# Power.net
KiCad netlist of a schematic drawn in Altium Designer
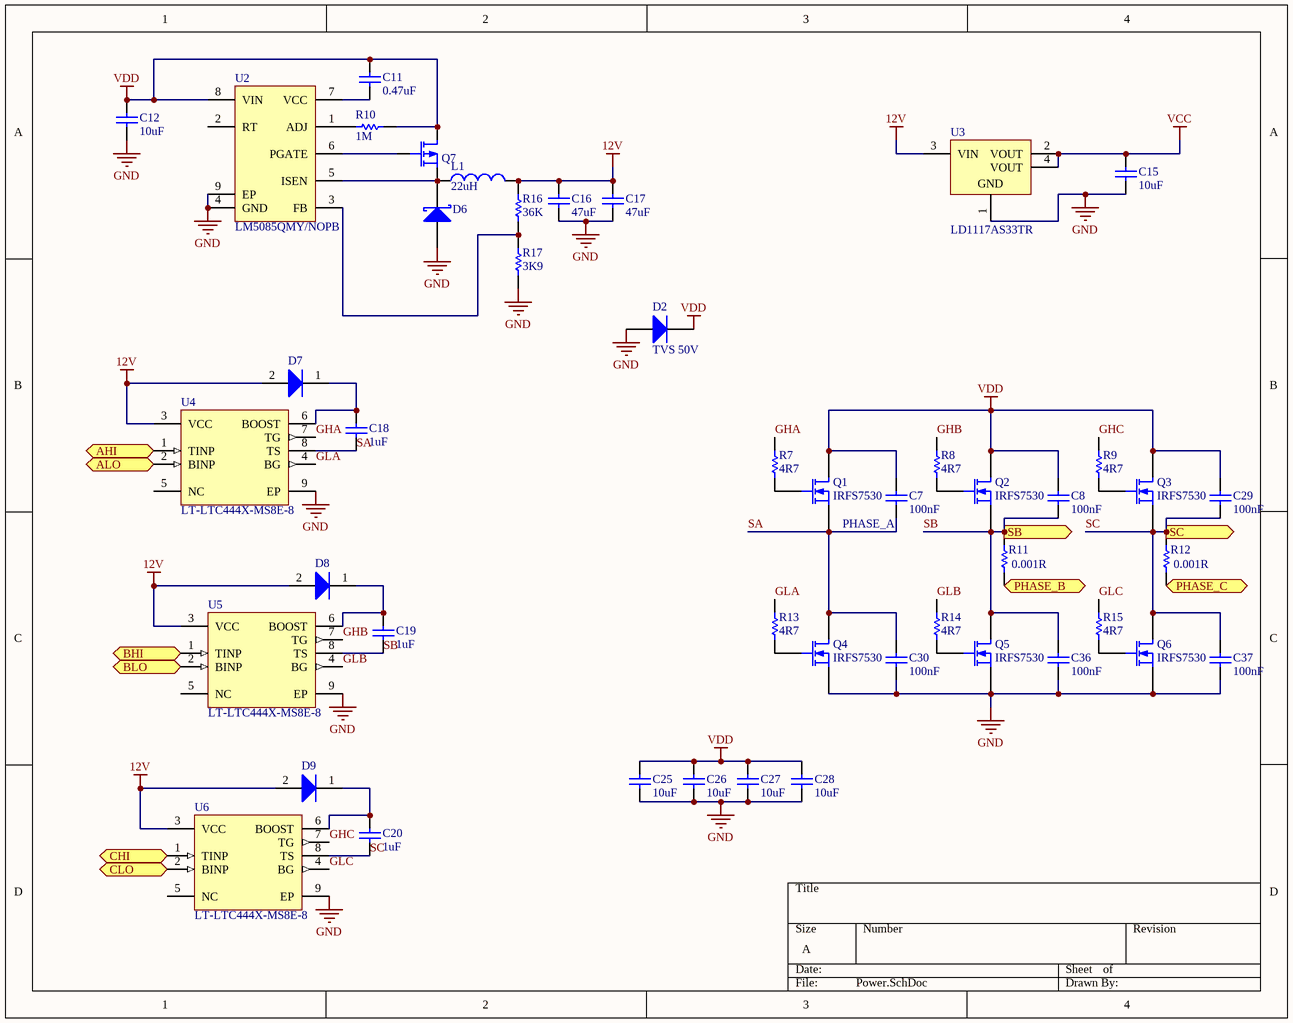
[diagram p0: Power.SchDoc]

(export (version "E")
  (design (tool "Eeschema 10.0.6"))
  (components
    (comp (ref "C7")
      (value "100nF")
      (footprint "CAPC0603(1608)100_L")
      (description "CAP 100nF 50V ±5% 0603 (1608 Metric) Thickness 1mm SMD")
      (fields (field (name "TOLERANCE") "Â±5%"))
      (libsource (lib "Altium Content Vault") (part "CAP"))
    )
    (comp (ref "C8")
      (value "100nF")
      (footprint "CAPC0603(1608)100_L")
      (description "CAP 100nF 50V ±5% 0603 (1608 Metric) Thickness 1mm SMD")
      (fields (field (name "TOLERANCE") "Â±5%"))
      (libsource (lib "Altium Content Vault") (part "CAP"))
    )
    (comp (ref "C11")
      (value "0.47uF")
      (footprint "CAPC0603(1608)100_L")
      (description "CAP 470nF 50V ±10% 0603 (1608 Metric) Thickness 1mm SMD")
      (fields (field (name "TOLERANCE") "Â±10%"))
      (libsource (lib "Altium Content Vault") (part "CAP"))
    )
    (comp (ref "C12")
      (value "10uF")
      (footprint "CAPC1206(3216)190_M")
      (description "CAP 10uF 50V Â±10% 1206 (3216 Metric) Thickness 1.9mm SMD")
      (fields (field (name "TOLERANCE") "Â±10%"))
      (libsource (lib "Altium Content Vault") (part "CMP-1037-04982-1"))
    )
    (comp (ref "C15")
      (value "10uF")
      (footprint "CAPC0603(1608)100_L")
      (description "CAP 10uF 6.3V ±10% 0603 (1608 Metric) Thickness 1mm SMD")
      (fields (field (name "TOLERANCE") "Â±10%"))
      (libsource (lib "Altium Content Vault") (part "CAP"))
    )
    (comp (ref "C16")
      (value "47uF")
      (footprint "CAPC1210(3225)280_L")
      (description "CAP 47uF 16V ±10% 1210 (3225 Metric) Thickness 2.8mm SMD")
      (fields (field (name "TOLERANCE") "Â±10%"))
      (libsource (lib "Altium Content Vault") (part "CAP"))
    )
    (comp (ref "C17")
      (value "47uF")
      (footprint "CAPC1210(3225)280_L")
      (description "CAP 47uF 16V ±10% 1210 (3225 Metric) Thickness 2.8mm SMD")
      (fields (field (name "TOLERANCE") "Â±10%"))
      (libsource (lib "Altium Content Vault") (part "CAP"))
    )
    (comp (ref "C18")
      (value "1uF")
      (footprint "CAPC0603(1608)100_M")
      (description "CAP 1uF 16V ±5% 0603 (1608 Metric) Thickness 1mm SMD")
      (fields (field (name "TOLERANCE") "Â±5%"))
      (libsource (lib "Altium Content Vault") (part "CAP"))
    )
    (comp (ref "C19")
      (value "1uF")
      (footprint "CAPC0603(1608)100_M")
      (description "CAP 1uF 16V ±5% 0603 (1608 Metric) Thickness 1mm SMD")
      (fields (field (name "TOLERANCE") "Â±5%"))
      (libsource (lib "Altium Content Vault") (part "CAP"))
    )
    (comp (ref "C20")
      (value "1uF")
      (footprint "CAPC0603(1608)100_M")
      (description "CAP 1uF 16V ±5% 0603 (1608 Metric) Thickness 1mm SMD")
      (fields (field (name "TOLERANCE") "Â±5%"))
      (libsource (lib "Altium Content Vault") (part "CAP"))
    )
    (comp (ref "C25")
      (value "10uF")
      (footprint "CAPC1206(3216)190_M")
      (description "CAP 10uF 50V Â±10% 1206 (3216 Metric) Thickness 1.9mm SMD")
      (fields (field (name "TOLERANCE") "Â±10%"))
      (libsource (lib "Altium Content Vault") (part "CMP-1037-04982-1"))
    )
    (comp (ref "C26")
      (value "10uF")
      (footprint "CAPC1206(3216)190_M")
      (description "CAP 10uF 50V Â±10% 1206 (3216 Metric) Thickness 1.9mm SMD")
      (fields (field (name "TOLERANCE") "Â±10%"))
      (libsource (lib "Altium Content Vault") (part "CAP"))
    )
    (comp (ref "C27")
      (value "10uF")
      (footprint "CAPC1206(3216)190_M")
      (description "CAP 10uF 50V Â±10% 1206 (3216 Metric) Thickness 1.9mm SMD")
      (fields (field (name "TOLERANCE") "Â±10%"))
      (libsource (lib "Altium Content Vault") (part "CAP"))
    )
    (comp (ref "C28")
      (value "10uF")
      (footprint "CAPC1206(3216)190_M")
      (description "CAP 10uF 50V Â±10% 1206 (3216 Metric) Thickness 1.9mm SMD")
      (fields (field (name "TOLERANCE") "Â±10%"))
      (libsource (lib "Altium Content Vault") (part "CMP-1037-04982-1"))
    )
    (comp (ref "C29")
      (value "100nF")
      (footprint "CAPC0603(1608)100_L")
      (description "CAP 100nF 50V ±5% 0603 (1608 Metric) Thickness 1mm SMD")
      (fields (field (name "TOLERANCE") "Â±5%"))
      (libsource (lib "Altium Content Vault") (part "CAP"))
    )
    (comp (ref "C30")
      (value "100nF")
      (footprint "CAPC0603(1608)100_L")
      (description "CAP 100nF 50V ±5% 0603 (1608 Metric) Thickness 1mm SMD")
      (fields (field (name "TOLERANCE") "Â±5%"))
      (libsource (lib "Altium Content Vault") (part "CAP"))
    )
    (comp (ref "C36")
      (value "100nF")
      (footprint "CAPC0603(1608)100_L")
      (description "CAP 100nF 50V ±5% 0603 (1608 Metric) Thickness 1mm SMD")
      (fields (field (name "TOLERANCE") "Â±5%"))
      (libsource (lib "Altium Content Vault") (part "CAP"))
    )
    (comp (ref "C37")
      (value "100nF")
      (footprint "CAPC0603(1608)100_L")
      (description "CAP 100nF 50V ±5% 0603 (1608 Metric) Thickness 1mm SMD")
      (fields (field (name "TOLERANCE") "Â±5%"))
      (libsource (lib "Altium Content Vault") (part "CAP"))
    )
    (comp (ref "D2")
      (value "TVS 50V")
      (footprint "VISH-DO-214AC-2_N")
      (fields
        (field (name "PARTNUMBER") "SMAJ45A-E3/61")
        (field (name "MANUFACTURER") "Vishay Semiconductor")
      )
      (libsource (lib "Altium Content Vault") (part "CMP-0548-00253-1"))
    )
    (comp (ref "D6")
      (value "~")
      (footprint "SMB")
      (description "Schottky Diode")
      (fields (field (name "PUBLISHER") "Altium Limited"))
      (libsource (lib "Miscellaneous Devices") (part "D Schottky"))
    )
    (comp (ref "D7")
      (value "~")
      (footprint "ONSC-SOD-323-2-477-02_V")
      (description "Silicon Hot-Carrier Diode, Schottky Barrier Diode, 2-Pin SOD-323, Pb-Free, Tape and Reel")
      (fields (field (name "PARTNUMBER") "MMDL301T1G") (field (name "MANUFACTURER") "On Semiconductor"))
      (libsource (lib "Altium Content Vault") (part "CMP-1051-00017-1"))
    )
    (comp (ref "D8")
      (value "~")
      (footprint "ONSC-SOD-323-2-477-02_V")
      (description "Silicon Hot-Carrier Diode, Schottky Barrier Diode, 2-Pin SOD-323, Pb-Free, Tape and Reel")
      (fields (field (name "PARTNUMBER") "MMDL301T1G") (field (name "MANUFACTURER") "On Semiconductor"))
      (libsource (lib "Altium Content Vault") (part "CMP-1051-00017-1"))
    )
    (comp (ref "D9")
      (value "~")
      (footprint "ONSC-SOD-323-2-477-02_V")
      (description "Silicon Hot-Carrier Diode, Schottky Barrier Diode, 2-Pin SOD-323, Pb-Free, Tape and Reel")
      (fields (field (name "PARTNUMBER") "MMDL301T1G") (field (name "MANUFACTURER") "On Semiconductor"))
      (libsource (lib "Altium Content Vault") (part "CMP-1051-00017-1"))
    )
    (comp (ref "L1")
      (value "22uH")
      (footprint "SDR0805-180ML")
      (description "Inductor")
      (fields (field (name "Comment") "SDR0805-180ML") (field (name "PUBLISHER") "Altium Limited"))
      (libsource (lib "Components") (part "SDR0805-180ML"))
    )
    (comp (ref "Q1")
      (value "IRFS7530")
      (footprint "DPAK127P1525X483-7N")
      (description "N-Channel MOSFET")
      (fields (field (name "PUBLISHER") "Altium Limited"))
      (libsource (lib "Components") (part "IRFS7530"))
    )
    (comp (ref "Q2")
      (value "IRFS7530")
      (footprint "DPAK127P1525X483-7N")
      (description "N-Channel MOSFET")
      (fields (field (name "PUBLISHER") "Altium Limited"))
      (libsource (lib "Components") (part "IRFS7530"))
    )
    (comp (ref "Q3")
      (value "IRFS7530")
      (footprint "DPAK127P1525X483-7N")
      (description "N-Channel MOSFET")
      (fields (field (name "PUBLISHER") "Altium Limited"))
      (libsource (lib "Components") (part "IRFS7530"))
    )
    (comp (ref "Q4")
      (value "IRFS7530")
      (footprint "DPAK127P1525X483-7N")
      (description "N-Channel MOSFET")
      (fields (field (name "PUBLISHER") "Altium Limited"))
      (libsource (lib "Components") (part "IRFS7530"))
    )
    (comp (ref "Q5")
      (value "IRFS7530")
      (footprint "DPAK127P1525X483-7N")
      (description "N-Channel MOSFET")
      (fields (field (name "PUBLISHER") "Altium Limited"))
      (libsource (lib "Components") (part "IRFS7530"))
    )
    (comp (ref "Q6")
      (value "IRFS7530")
      (footprint "DPAK127P1525X483-7N")
      (description "N-Channel MOSFET")
      (fields (field (name "PUBLISHER") "Altium Limited"))
      (libsource (lib "Components") (part "IRFS7530"))
    )
    (comp (ref "Q7")
      (value "MOSFET-P")
      (footprint "SOIC127P600X175-8N")
      (description "P-Channel MOSFET")
      (fields (field (name "PUBLISHER") "Altium Limited"))
      (libsource (lib "Components") (part "MOSFET-P"))
    )
    (comp (ref "R7")
      (value "4R7")
      (footprint "RESC0603(1608)_N")
      (description "4R7 0.1W 5% 0603 (1608 Metric)  SMD")
      (fields (field (name "POWER") "0.1 W") (field (name "TOLERANCE") "5 %"))
      (libsource (lib "Altium Content Vault") (part "CMP-1012-00018-1"))
    )
    (comp (ref "R8")
      (value "4R7")
      (footprint "RESC0603(1608)_N")
      (description "4R7 0.1W 5% 0603 (1608 Metric)  SMD")
      (fields (field (name "POWER") "0.1 W") (field (name "TOLERANCE") "5 %"))
      (libsource (lib "Altium Content Vault") (part "CMP-1012-00018-1"))
    )
    (comp (ref "R9")
      (value "4R7")
      (footprint "RESC0603(1608)_N")
      (description "4R7 0.1W 5% 0603 (1608 Metric)  SMD")
      (fields (field (name "POWER") "0.1 W") (field (name "TOLERANCE") "5 %"))
      (libsource (lib "Altium Content Vault") (part "CMP-1012-00018-1"))
    )
    (comp (ref "R10")
      (value "1M")
      (footprint "RESC0603(1608)_M")
      (description "1M 0.1W 5% 0603 (1608 Metric)  SMD")
      (fields (field (name "POWER") "0.1 W") (field (name "TOLERANCE") "5 %"))
      (libsource (lib "Altium Content Vault") (part "RES"))
    )
    (comp (ref "R11")
      (value "0.001R")
      (footprint "Shunt")
      (fields (field (name "PUBLISHER") "Altium Limited"))
      (libsource (lib "Components") (part "Shunt"))
    )
    (comp (ref "R12")
      (value "0.001R")
      (footprint "Shunt")
      (description "Resistor")
      (fields (field (name "PUBLISHER") "Altium Limited"))
      (libsource (lib "Components") (part "Shunt"))
    )
    (comp (ref "R13")
      (value "4R7")
      (footprint "RESC0603(1608)_N")
      (description "4R7 0.1W 5% 0603 (1608 Metric)  SMD")
      (fields (field (name "POWER") "0.1 W") (field (name "TOLERANCE") "5 %"))
      (libsource (lib "Altium Content Vault") (part "CMP-1012-00018-1"))
    )
    (comp (ref "R14")
      (value "4R7")
      (footprint "RESC0603(1608)_N")
      (description "4R7 0.1W 5% 0603 (1608 Metric)  SMD")
      (fields (field (name "POWER") "0.1 W") (field (name "TOLERANCE") "5 %"))
      (libsource (lib "Altium Content Vault") (part "CMP-1012-00018-1"))
    )
    (comp (ref "R15")
      (value "4R7")
      (footprint "RESC0603(1608)_N")
      (description "4R7 0.1W 5% 0603 (1608 Metric)  SMD")
      (fields (field (name "POWER") "0.1 W") (field (name "TOLERANCE") "5 %"))
      (libsource (lib "Altium Content Vault") (part "CMP-1012-00018-1"))
    )
    (comp (ref "R16")
      (value "36K")
      (footprint "RESC0603(1608)_M")
      (description "36K 0.1W 5% 0603 (1608 Metric)  SMD")
      (fields (field (name "TOLERANCE") "5 %") (field (name "POWER") "0.1 W"))
      (libsource (lib "Altium Content Vault") (part "CMP-1012-00111-1"))
    )
    (comp (ref "R17")
      (value "3K9")
      (footprint "RESC0603(1608)_L")
      (description "3K9 0.1W 5% 0603 (1608 Metric)  SMD")
      (fields (field (name "POWER") "0.1 W") (field (name "TOLERANCE") "5 %"))
      (libsource (lib "Altium Content Vault") (part "CMP-1012-00088-1"))
    )
    (comp (ref "U2")
      (value "LM5085QMY/NOPB")
      (footprint "MUY08A_L")
      (description "75V Constant On-Time PFET Buck Switching Controller, 8-pin eMSOP, Pb-Free")
      (fields (field (name "MANUFACTURER") "National Semiconductor"))
      (libsource (lib "Altium Content Vault") (part "PM-SWREG-LM5085-9"))
    )
    (comp (ref "U3")
      (value "LD1117AS33TR")
      (footprint "SOT-223_N")
      (description "1A, Low Drop Positive Voltage Regulator, 3.3V, 4-Pin SOT-223, Tape and Reel")
      (libsource (lib "Altium Content Vault") (part "PM-REG-LD1117-SOT4"))
    )
    (comp (ref "U4")
      (value "LT-LTC444X-MS8E-8")
      (footprint "LT-MS8E-8-EDP_L")
      (libsource (lib "Components") (part "LT-LTC444X-MS8E-8"))
    )
    (comp (ref "U5")
      (value "LT-LTC444X-MS8E-8")
      (footprint "LT-MS8E-8-EDP_L")
      (libsource (lib "Components") (part "LT-LTC444X-MS8E-8"))
    )
    (comp (ref "U6")
      (value "LT-LTC444X-MS8E-8")
      (footprint "LT-MS8E-8-EDP_L")
      (libsource (lib "Components") (part "LT-LTC444X-MS8E-8"))
    )
  )
  (nets
    (net (code "1") (name "/AHI") (class "Default")
      (node (ref "U4") (pin "1") (pinfunction "TINP_1") (pintype "input"))
    )
    (net (code "2") (name "/ALO") (class "Default")
      (node (ref "U4") (pin "2") (pinfunction "BINP_2") (pintype "input"))
    )
    (net (code "3") (name "/BHI") (class "Default")
      (node (ref "U5") (pin "1") (pinfunction "TINP_1") (pintype "input"))
    )
    (net (code "4") (name "/BLO") (class "Default")
      (node (ref "U5") (pin "2") (pinfunction "BINP_2") (pintype "input"))
    )
    (net (code "5") (name "/CHI") (class "Default")
      (node (ref "U6") (pin "1") (pinfunction "TINP_1") (pintype "input"))
    )
    (net (code "6") (name "/CLO") (class "Default")
      (node (ref "U6") (pin "2") (pinfunction "BINP_2") (pintype "input"))
    )
    (net (code "7") (name "/GHA") (class "Default")
      (node (ref "R7") (pin "2") (pinfunction "2_2") (pintype "passive"))
      (node (ref "U4") (pin "7") (pinfunction "TG_7") (pintype "output"))
    )
    (net (code "8") (name "/GHB") (class "Default")
      (node (ref "R8") (pin "2") (pinfunction "2_2") (pintype "passive"))
      (node (ref "U5") (pin "7") (pinfunction "TG_7") (pintype "output"))
    )
    (net (code "9") (name "/GHC") (class "Default")
      (node (ref "R9") (pin "2") (pinfunction "2_2") (pintype "passive"))
      (node (ref "U6") (pin "7") (pinfunction "TG_7") (pintype "output"))
    )
    (net (code "10") (name "/GLA") (class "Default")
      (node (ref "R13") (pin "2") (pinfunction "2_2") (pintype "passive"))
      (node (ref "U4") (pin "4") (pinfunction "BG_4") (pintype "output"))
    )
    (net (code "11") (name "/GLB") (class "Default")
      (node (ref "R14") (pin "2") (pinfunction "2_2") (pintype "passive"))
      (node (ref "U5") (pin "4") (pinfunction "BG_4") (pintype "output"))
    )
    (net (code "12") (name "/GLC") (class "Default")
      (node (ref "R15") (pin "2") (pinfunction "2_2") (pintype "passive"))
      (node (ref "U6") (pin "4") (pinfunction "BG_4") (pintype "output"))
    )
    (net (code "13") (name "/PHASE_B") (class "Default")
      (node (ref "R11") (pin "1") (pinfunction "1_1") (pintype "passive"))
    )
    (net (code "14") (name "/PHASE_C") (class "Default")
      (node (ref "R12") (pin "1") (pinfunction "1_1") (pintype "passive"))
    )
    (net (code "15") (name "/SA") (class "Default")
      (node (ref "C18") (pin "1") (pinfunction "1_1") (pintype "passive"))
      (node (ref "C30") (pin "2") (pinfunction "2_2") (pintype "passive"))
      (node (ref "C7") (pin "1") (pinfunction "1_1") (pintype "passive"))
      (node (ref "Q1") (pin "3") (pinfunction "S_3") (pintype "passive"))
      (node (ref "Q4") (pin "1") (pinfunction "D_1") (pintype "passive"))
      (node (ref "U4") (pin "8") (pinfunction "TS_8") (pintype "passive"))
    )
    (net (code "16") (name "/SB") (class "Default")
      (node (ref "C19") (pin "1") (pinfunction "1_1") (pintype "passive"))
      (node (ref "C36") (pin "2") (pinfunction "2_2") (pintype "passive"))
      (node (ref "C8") (pin "1") (pinfunction "1_1") (pintype "passive"))
      (node (ref "Q2") (pin "3") (pinfunction "S_3") (pintype "passive"))
      (node (ref "Q5") (pin "1") (pinfunction "D_1") (pintype "passive"))
      (node (ref "R11") (pin "2") (pinfunction "2_2") (pintype "passive"))
      (node (ref "U5") (pin "8") (pinfunction "TS_8") (pintype "passive"))
    )
    (net (code "17") (name "/SC") (class "Default")
      (node (ref "C20") (pin "1") (pinfunction "1_1") (pintype "passive"))
      (node (ref "C29") (pin "1") (pinfunction "1_1") (pintype "passive"))
      (node (ref "C37") (pin "2") (pinfunction "2_2") (pintype "passive"))
      (node (ref "Q3") (pin "3") (pinfunction "S_3") (pintype "passive"))
      (node (ref "Q6") (pin "1") (pinfunction "D_1") (pintype "passive"))
      (node (ref "R12") (pin "2") (pinfunction "2_2") (pintype "passive"))
      (node (ref "U6") (pin "8") (pinfunction "TS_8") (pintype "passive"))
    )
    (net (code "18") (name "12V") (class "Default")
      (node (ref "C16") (pin "2") (pinfunction "2_2") (pintype "passive"))
      (node (ref "C17") (pin "2") (pinfunction "2_2") (pintype "passive"))
      (node (ref "D7") (pin "2") (pinfunction "A_2") (pintype "passive"))
      (node (ref "D8") (pin "2") (pinfunction "A_2") (pintype "passive"))
      (node (ref "D9") (pin "2") (pinfunction "A_2") (pintype "passive"))
      (node (ref "L1") (pin "2") (pinfunction "2_2") (pintype "passive"))
      (node (ref "R16") (pin "2") (pinfunction "2_2") (pintype "passive"))
      (node (ref "U3") (pin "3") (pinfunction "VIN_3") (pintype "power_in"))
      (node (ref "U4") (pin "3") (pinfunction "VCC_3") (pintype "power_in"))
      (node (ref "U5") (pin "3") (pinfunction "VCC_3") (pintype "power_in"))
      (node (ref "U6") (pin "3") (pinfunction "VCC_3") (pintype "power_in"))
    )
    (net (code "19") (name "GND") (class "Default")
      (node (ref "C12") (pin "1") (pinfunction "1_1") (pintype "passive"))
      (node (ref "C15") (pin "1") (pinfunction "1_1") (pintype "passive"))
      (node (ref "C16") (pin "1") (pinfunction "1_1") (pintype "passive"))
      (node (ref "C17") (pin "1") (pinfunction "1_1") (pintype "passive"))
      (node (ref "C25") (pin "1") (pinfunction "1_1") (pintype "passive"))
      (node (ref "C26") (pin "1") (pinfunction "1_1") (pintype "passive"))
      (node (ref "C27") (pin "1") (pinfunction "1_1") (pintype "passive"))
      (node (ref "C28") (pin "1") (pinfunction "1_1") (pintype "passive"))
      (node (ref "C30") (pin "1") (pinfunction "1_1") (pintype "passive"))
      (node (ref "C36") (pin "1") (pinfunction "1_1") (pintype "passive"))
      (node (ref "C37") (pin "1") (pinfunction "1_1") (pintype "passive"))
      (node (ref "D2") (pin "2") (pinfunction "A_2") (pintype "passive"))
      (node (ref "D6") (pin "1") (pinfunction "A_1") (pintype "passive"))
      (node (ref "Q4") (pin "3") (pinfunction "S_3") (pintype "passive"))
      (node (ref "Q5") (pin "3") (pinfunction "S_3") (pintype "passive"))
      (node (ref "Q6") (pin "3") (pinfunction "S_3") (pintype "passive"))
      (node (ref "R17") (pin "1") (pinfunction "1_1") (pintype "passive"))
      (node (ref "U2") (pin "4") (pinfunction "GND_4") (pintype "power_in"))
      (node (ref "U2") (pin "9") (pinfunction "EP_9") (pintype "passive"))
      (node (ref "U3") (pin "1") (pinfunction "GND_1") (pintype "power_in"))
      (node (ref "U4") (pin "9") (pinfunction "EP_9") (pintype "power_in"))
      (node (ref "U5") (pin "9") (pinfunction "EP_9") (pintype "power_in"))
      (node (ref "U6") (pin "9") (pinfunction "EP_9") (pintype "power_in"))
    )
    (net (code "20") (name "Net-(D6-K)") (class "Default")
      (node (ref "D6") (pin "2") (pinfunction "K_2") (pintype "passive"))
      (node (ref "L1") (pin "1") (pinfunction "1_1") (pintype "passive"))
      (node (ref "Q7") (pin "3") (pinfunction "S_3") (pintype "passive"))
      (node (ref "U2") (pin "5") (pinfunction "ISEN_5") (pintype "passive"))
    )
    (net (code "21") (name "Net-(D7-K)") (class "Default")
      (node (ref "C18") (pin "2") (pinfunction "2_2") (pintype "passive"))
      (node (ref "D7") (pin "1") (pinfunction "K_1") (pintype "passive"))
      (node (ref "U4") (pin "6") (pinfunction "BOOST_6") (pintype "passive"))
    )
    (net (code "22") (name "Net-(D8-K)") (class "Default")
      (node (ref "C19") (pin "2") (pinfunction "2_2") (pintype "passive"))
      (node (ref "D8") (pin "1") (pinfunction "K_1") (pintype "passive"))
      (node (ref "U5") (pin "6") (pinfunction "BOOST_6") (pintype "passive"))
    )
    (net (code "23") (name "Net-(D9-K)") (class "Default")
      (node (ref "C20") (pin "2") (pinfunction "2_2") (pintype "passive"))
      (node (ref "D9") (pin "1") (pinfunction "K_1") (pintype "passive"))
      (node (ref "U6") (pin "6") (pinfunction "BOOST_6") (pintype "passive"))
    )
    (net (code "24") (name "Net-(Q1-G)") (class "Default")
      (node (ref "Q1") (pin "2") (pinfunction "G_2") (pintype "passive"))
      (node (ref "R7") (pin "1") (pinfunction "1_1") (pintype "passive"))
    )
    (net (code "25") (name "Net-(Q2-G)") (class "Default")
      (node (ref "Q2") (pin "2") (pinfunction "G_2") (pintype "passive"))
      (node (ref "R8") (pin "1") (pinfunction "1_1") (pintype "passive"))
    )
    (net (code "26") (name "Net-(Q3-G)") (class "Default")
      (node (ref "Q3") (pin "2") (pinfunction "G_2") (pintype "passive"))
      (node (ref "R9") (pin "1") (pinfunction "1_1") (pintype "passive"))
    )
    (net (code "27") (name "Net-(Q4-G)") (class "Default")
      (node (ref "Q4") (pin "2") (pinfunction "G_2") (pintype "passive"))
      (node (ref "R13") (pin "1") (pinfunction "1_1") (pintype "passive"))
    )
    (net (code "28") (name "Net-(Q5-G)") (class "Default")
      (node (ref "Q5") (pin "2") (pinfunction "G_2") (pintype "passive"))
      (node (ref "R14") (pin "1") (pinfunction "1_1") (pintype "passive"))
    )
    (net (code "29") (name "Net-(Q6-G)") (class "Default")
      (node (ref "Q6") (pin "2") (pinfunction "G_2") (pintype "passive"))
      (node (ref "R15") (pin "1") (pinfunction "1_1") (pintype "passive"))
    )
    (net (code "30") (name "Net-(Q7-G)") (class "Default")
      (node (ref "Q7") (pin "1") (pinfunction "G_1") (pintype "passive"))
      (node (ref "U2") (pin "6") (pinfunction "PGATE_6") (pintype "passive"))
    )
    (net (code "31") (name "Net-(U2-ADJ)") (class "Default")
      (node (ref "R10") (pin "1") (pinfunction "1_1") (pintype "passive"))
      (node (ref "U2") (pin "1") (pinfunction "ADJ_1") (pintype "passive"))
    )
    (net (code "32") (name "Net-(U2-FB)") (class "Default")
      (node (ref "R16") (pin "1") (pinfunction "1_1") (pintype "passive"))
      (node (ref "R17") (pin "2") (pinfunction "2_2") (pintype "passive"))
      (node (ref "U2") (pin "3") (pinfunction "FB_3") (pintype "passive"))
    )
    (net (code "33") (name "Net-(U2-VCC)") (class "Default")
      (node (ref "C11") (pin "1") (pinfunction "1_1") (pintype "passive"))
      (node (ref "U2") (pin "7") (pinfunction "VCC_7") (pintype "power_in"))
    )
    (net (code "34") (name "VCC") (class "Default")
      (node (ref "C15") (pin "2") (pinfunction "2_2") (pintype "passive"))
      (node (ref "U3") (pin "2") (pinfunction "VOUT_2") (pintype "power_in"))
      (node (ref "U3") (pin "4") (pinfunction "VOUT_4") (pintype "power_in"))
    )
    (net (code "35") (name "VDD") (class "Default")
      (node (ref "C11") (pin "2") (pinfunction "2_2") (pintype "passive"))
      (node (ref "C12") (pin "2") (pinfunction "2_2") (pintype "passive"))
      (node (ref "C25") (pin "2") (pinfunction "2_2") (pintype "passive"))
      (node (ref "C26") (pin "2") (pinfunction "2_2") (pintype "passive"))
      (node (ref "C27") (pin "2") (pinfunction "2_2") (pintype "passive"))
      (node (ref "C28") (pin "2") (pinfunction "2_2") (pintype "passive"))
      (node (ref "C29") (pin "2") (pinfunction "2_2") (pintype "passive"))
      (node (ref "C7") (pin "2") (pinfunction "2_2") (pintype "passive"))
      (node (ref "C8") (pin "2") (pinfunction "2_2") (pintype "passive"))
      (node (ref "D2") (pin "1") (pinfunction "K_1") (pintype "passive"))
      (node (ref "Q1") (pin "1") (pinfunction "D_1") (pintype "passive"))
      (node (ref "Q2") (pin "1") (pinfunction "D_1") (pintype "passive"))
      (node (ref "Q3") (pin "1") (pinfunction "D_1") (pintype "passive"))
      (node (ref "Q7") (pin "2") (pinfunction "D_2") (pintype "passive"))
      (node (ref "R10") (pin "2") (pinfunction "2_2") (pintype "passive"))
      (node (ref "U2") (pin "8") (pinfunction "VIN_8") (pintype "passive"))
    )
    (net (code "36") (name "unconnected-(U2-RT-Pad2)") (class "Default")
      (node (ref "U2") (pin "2") (pinfunction "RT_2") (pintype "passive"))
    )
    (net (code "37") (name "unconnected-(U4-NC-Pad5)") (class "Default")
      (node (ref "U4") (pin "5") (pinfunction "NC_5") (pintype "passive"))
    )
    (net (code "38") (name "unconnected-(U5-NC-Pad5)") (class "Default")
      (node (ref "U5") (pin "5") (pinfunction "NC_5") (pintype "passive"))
    )
    (net (code "39") (name "unconnected-(U6-NC-Pad5)") (class "Default")
      (node (ref "U6") (pin "5") (pinfunction "NC_5") (pintype "passive"))
    )
  )
)
